# DSP_DIO.net
KiCad netlist of a schematic drawn in Altium Designer
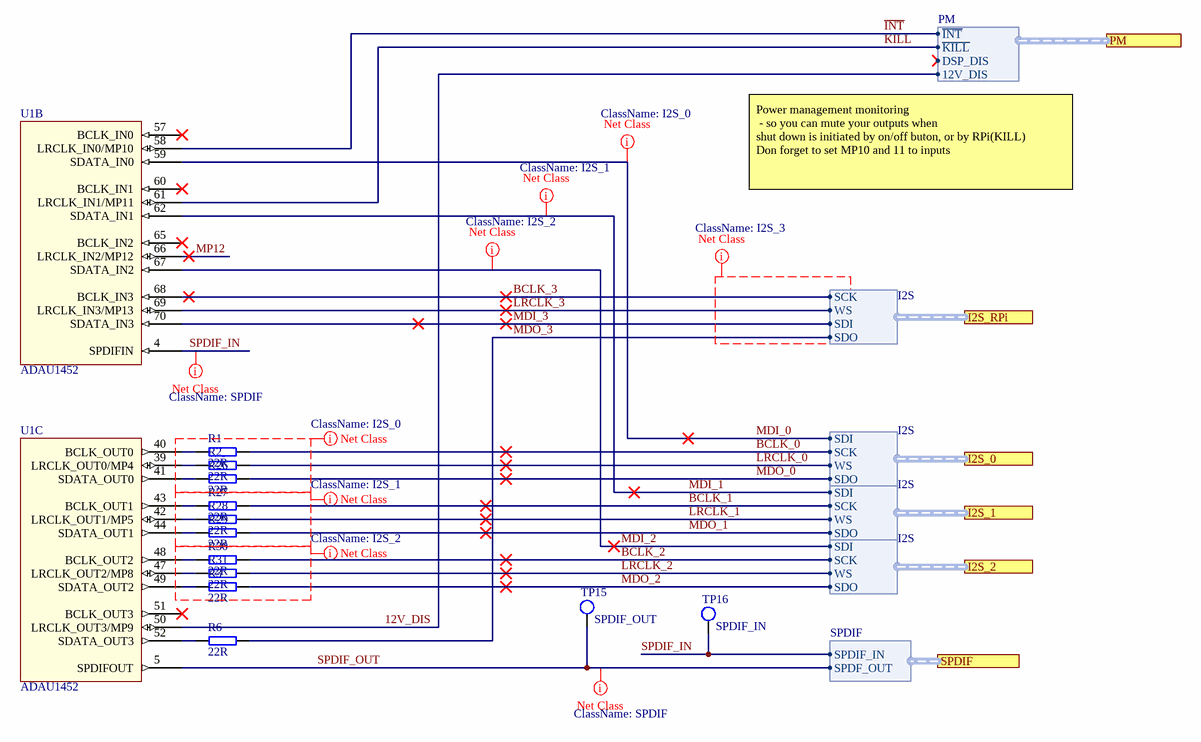
[diagram p0: DSP_DIO.SchDoc]

(export (version "E")
  (design (tool "Eeschema 10.0.6"))
  (components
    (comp (ref "R1")
      (value "22R")
      (footprint "RESC1608X06N(SMR0603)")
      (description "Chip Resistor")
      (fields (field (name "AUTHOR") "JP/10.06.2014"))
      (libsource (lib "JP_R") (part "22R-100mW-0603-ThickFilm"))
    )
    (comp (ref "R2")
      (value "22R")
      (footprint "RESC1608X06N(SMR0603)")
      (description "Chip Resistor")
      (fields (field (name "AUTHOR") "JP/10.06.2014"))
      (libsource (lib "JP_R") (part "22R-100mW-0603-ThickFilm"))
    )
    (comp (ref "R3")
      (value "22R")
      (footprint "RESC1608X06N(SMR0603)")
      (description "Chip Resistor")
      (fields (field (name "AUTHOR") "JP/10.06.2014"))
      (libsource (lib "JP_R") (part "22R-100mW-0603-ThickFilm"))
    )
    (comp (ref "R6")
      (value "22R")
      (footprint "RESC1608X06N(SMR0603)")
      (description "Chip Resistor")
      (fields (field (name "AUTHOR") "JP/10.06.2014"))
      (libsource (lib "JP_R") (part "22R-100mW-0603-ThickFilm"))
    )
    (comp (ref "R26")
      (value "22R")
      (footprint "RESC1608X06N(SMR0603)")
      (description "Chip Resistor")
      (fields (field (name "AUTHOR") "JP/10.06.2014"))
      (libsource (lib "JP_R") (part "22R-100mW-0603-ThickFilm"))
    )
    (comp (ref "R27")
      (value "22R")
      (footprint "RESC1608X06N(SMR0603)")
      (description "Chip Resistor")
      (fields (field (name "AUTHOR") "JP/10.06.2014"))
      (libsource (lib "JP_R") (part "22R-100mW-0603-ThickFilm"))
    )
    (comp (ref "R28")
      (value "22R")
      (footprint "RESC1608X06N(SMR0603)")
      (description "Chip Resistor")
      (fields (field (name "AUTHOR") "JP/10.06.2014"))
      (libsource (lib "JP_R") (part "22R-100mW-0603-ThickFilm"))
    )
    (comp (ref "R29")
      (value "22R")
      (footprint "RESC1608X06N(SMR0603)")
      (description "Chip Resistor")
      (fields (field (name "AUTHOR") "JP/10.06.2014"))
      (libsource (lib "JP_R") (part "22R-100mW-0603-ThickFilm"))
    )
    (comp (ref "R30")
      (value "22R")
      (footprint "RESC1608X06N(SMR0603)")
      (description "Chip Resistor")
      (fields (field (name "AUTHOR") "JP/10.06.2014"))
      (libsource (lib "JP_R") (part "22R-100mW-0603-ThickFilm"))
    )
    (comp (ref "R31")
      (value "22R")
      (footprint "RESC1608X06N(SMR0603)")
      (description "Chip Resistor")
      (fields (field (name "AUTHOR") "JP/10.06.2014"))
      (libsource (lib "JP_R") (part "22R-100mW-0603-ThickFilm"))
    )
    (comp (ref "TP15")
      (value "SPDIF_OUT")
      (footprint "TP_0.8/0.4_ROUND")
      (description "Testpoint - VIA")
      (libsource (lib "JP_CONN") (part "TEST_POINT_VIA"))
    )
    (comp (ref "TP16")
      (value "SPDIF_IN")
      (footprint "TP_0.8/0.4_ROUND")
      (description "Testpoint - VIA")
      (libsource (lib "JP_CONN") (part "TEST_POINT_VIA"))
    )
    (comp (ref "U1")
      (value "ADAU1452")
      (footprint "CP_72_6-handsoldering")
      (libsource (lib "JP_IC") (part "ADAU1452"))
    )
  )
  (nets
    (net (code "4") (name "/12V_DIS") (class "Default")
      (node (ref "U1") (pin "50") (pinfunction "LRCLK_OUT3/MP9_50") (pintype "bidirectional"))
    )
    (net (code "5") (name "/BCLK_0") (class "Default")
      (node (ref "R1") (pin "1") (pinfunction "1_1") (pintype "passive"))
    )
    (net (code "6") (name "/BCLK_1") (class "Default")
      (node (ref "R27") (pin "1") (pinfunction "1_1") (pintype "passive"))
    )
    (net (code "7") (name "/BCLK_2") (class "Default")
      (node (ref "R30") (pin "1") (pinfunction "1_1") (pintype "passive"))
    )
    (net (code "8") (name "/BCLK_3") (class "Default")
      (node (ref "U1") (pin "68") (pinfunction "BCLK_IN3_68") (pintype "input"))
    )
    (net (code "9") (name "/LRCLK_0") (class "Default")
      (node (ref "R2") (pin "1") (pinfunction "1_1") (pintype "passive"))
    )
    (net (code "10") (name "/LRCLK_1") (class "Default")
      (node (ref "R28") (pin "1") (pinfunction "1_1") (pintype "passive"))
    )
    (net (code "11") (name "/LRCLK_2") (class "Default")
      (node (ref "R31") (pin "1") (pinfunction "1_1") (pintype "passive"))
    )
    (net (code "12") (name "/LRCLK_3") (class "Default")
      (node (ref "U1") (pin "69") (pinfunction "LRCLK_IN3/MP13_69") (pintype "bidirectional"))
    )
    (net (code "13") (name "/MDI_0") (class "Default")
      (node (ref "U1") (pin "59") (pinfunction "SDATA_IN0_59") (pintype "input"))
    )
    (net (code "14") (name "/MDI_1") (class "Default")
      (node (ref "U1") (pin "62") (pinfunction "SDATA_IN1_62") (pintype "input"))
    )
    (net (code "15") (name "/MDI_2") (class "Default")
      (node (ref "U1") (pin "67") (pinfunction "SDATA_IN2_67") (pintype "input"))
    )
    (net (code "16") (name "/MDI_3") (class "Default")
      (node (ref "U1") (pin "70") (pinfunction "SDATA_IN3_70") (pintype "input"))
    )
    (net (code "17") (name "/MDO_0") (class "Default")
      (node (ref "R26") (pin "1") (pinfunction "1_1") (pintype "passive"))
    )
    (net (code "18") (name "/MDO_1") (class "Default")
      (node (ref "R29") (pin "1") (pinfunction "1_1") (pintype "passive"))
    )
    (net (code "19") (name "/MDO_2") (class "Default")
      (node (ref "R3") (pin "1") (pinfunction "1_1") (pintype "passive"))
    )
    (net (code "20") (name "/MDO_3") (class "Default")
      (node (ref "R6") (pin "1") (pinfunction "1_1") (pintype "passive"))
    )
    (net (code "21") (name "/MP12") (class "Default")
      (node (ref "U1") (pin "66") (pinfunction "LRCLK_IN2/MP12_66") (pintype "bidirectional"))
    )
    (net (code "22") (name "/SPDIF_IN") (class "Default")
      (node (ref "TP16") (pin "1") (pintype "passive"))
      (node (ref "U1") (pin "4") (pinfunction "SPDIFIN_4") (pintype "input"))
    )
    (net (code "23") (name "/SPDIF_OUT") (class "Default")
      (node (ref "TP15") (pin "1") (pintype "passive"))
      (node (ref "U1") (pin "5") (pinfunction "SPDIFOUT_5") (pintype "output"))
    )
    (net (code "27") (name "/~{INT}") (class "Default")
      (node (ref "U1") (pin "58") (pinfunction "LRCLK_IN0/MP10_58") (pintype "bidirectional"))
    )
    (net (code "28") (name "/~{KILL}") (class "Default")
      (node (ref "U1") (pin "61") (pinfunction "LRCLK_IN1/MP11_61") (pintype "bidirectional"))
    )
    (net (code "29") (name "Net-(U1C-BCLK_OUT0)") (class "Default")
      (node (ref "R1") (pin "2") (pinfunction "2_2") (pintype "passive"))
      (node (ref "U1") (pin "40") (pinfunction "BCLK_OUT0_40") (pintype "output"))
    )
    (net (code "30") (name "Net-(U1C-BCLK_OUT1)") (class "Default")
      (node (ref "R27") (pin "2") (pinfunction "2_2") (pintype "passive"))
      (node (ref "U1") (pin "43") (pinfunction "BCLK_OUT1_43") (pintype "output"))
    )
    (net (code "31") (name "Net-(U1C-BCLK_OUT2)") (class "Default")
      (node (ref "R30") (pin "2") (pinfunction "2_2") (pintype "passive"))
      (node (ref "U1") (pin "48") (pinfunction "BCLK_OUT2_48") (pintype "output"))
    )
    (net (code "32") (name "Net-(U1C-LRCLK_OUT0{slash}MP4)") (class "Default")
      (node (ref "R2") (pin "2") (pinfunction "2_2") (pintype "passive"))
      (node (ref "U1") (pin "39") (pinfunction "LRCLK_OUT0/MP4_39") (pintype "bidirectional"))
    )
    (net (code "33") (name "Net-(U1C-LRCLK_OUT1{slash}MP5)") (class "Default")
      (node (ref "R28") (pin "2") (pinfunction "2_2") (pintype "passive"))
      (node (ref "U1") (pin "42") (pinfunction "LRCLK_OUT1/MP5_42") (pintype "bidirectional"))
    )
    (net (code "34") (name "Net-(U1C-LRCLK_OUT2{slash}MP8)") (class "Default")
      (node (ref "R31") (pin "2") (pinfunction "2_2") (pintype "passive"))
      (node (ref "U1") (pin "47") (pinfunction "LRCLK_OUT2/MP8_47") (pintype "bidirectional"))
    )
    (net (code "35") (name "Net-(U1C-SDATA_OUT0)") (class "Default")
      (node (ref "R26") (pin "2") (pinfunction "2_2") (pintype "passive"))
      (node (ref "U1") (pin "41") (pinfunction "SDATA_OUT0_41") (pintype "output"))
    )
    (net (code "36") (name "Net-(U1C-SDATA_OUT1)") (class "Default")
      (node (ref "R29") (pin "2") (pinfunction "2_2") (pintype "passive"))
      (node (ref "U1") (pin "44") (pinfunction "SDATA_OUT1_44") (pintype "output"))
    )
    (net (code "37") (name "Net-(U1C-SDATA_OUT2)") (class "Default")
      (node (ref "R3") (pin "2") (pinfunction "2_2") (pintype "passive"))
      (node (ref "U1") (pin "49") (pinfunction "SDATA_OUT2_49") (pintype "output"))
    )
    (net (code "38") (name "Net-(U1C-SDATA_OUT3)") (class "Default")
      (node (ref "R6") (pin "2") (pinfunction "2_2") (pintype "passive"))
      (node (ref "U1") (pin "52") (pinfunction "SDATA_OUT3_52") (pintype "output"))
    )
    (net (code "39") (name "unconnected-(U1B-BCLK_IN0-Pad57)") (class "Default")
      (node (ref "U1") (pin "57") (pinfunction "BCLK_IN0_57") (pintype "input+no_connect"))
    )
    (net (code "40") (name "unconnected-(U1B-BCLK_IN1-Pad60)") (class "Default")
      (node (ref "U1") (pin "60") (pinfunction "BCLK_IN1_60") (pintype "input+no_connect"))
    )
    (net (code "41") (name "unconnected-(U1B-BCLK_IN2-Pad65)") (class "Default")
      (node (ref "U1") (pin "65") (pinfunction "BCLK_IN2_65") (pintype "input+no_connect"))
    )
    (net (code "42") (name "unconnected-(U1C-BCLK_OUT3-Pad51)") (class "Default")
      (node (ref "U1") (pin "51") (pinfunction "BCLK_OUT3_51") (pintype "output+no_connect"))
    )
  )
)
